# adapter.net
KiCad netlist of a schematic drawn in EAGLE
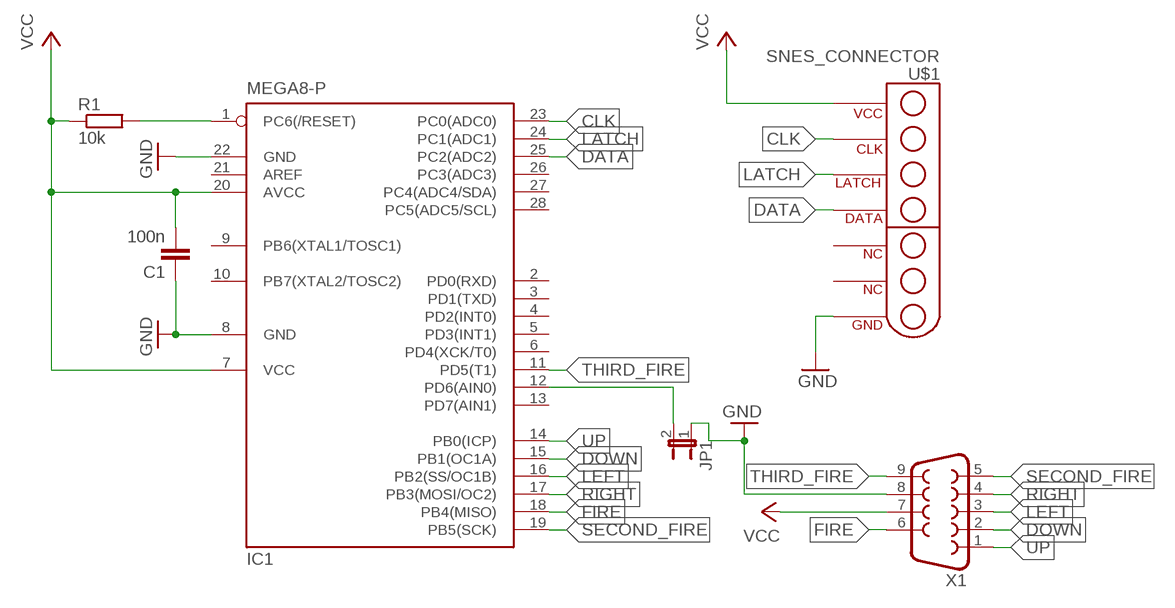
[diagram p0: schematic, sheet 1]

(export (version "E")
  (design (tool "Eeschema 10.0.6"))
  (components
    (comp (ref "C1")
      (value "100n")
      (footprint "eagle-import:C025-025X050")
      (libsource (lib "eagle-import") (part "C-EU025-025X050"))
    )
    (comp (ref "IC1")
      (value "MEGA8-P")
      (footprint "eagle-import:DIL28-3")
      (libsource (lib "eagle-import") (part "MEGA8-P"))
    )
    (comp (ref "JP1")
      (value "JP1E")
      (footprint "eagle-import:JP1")
      (libsource (lib "eagle-import") (part "JP1E"))
    )
    (comp (ref "R1")
      (value "10k")
      (footprint "eagle-import:0207_10")
      (libsource (lib "eagle-import") (part "R-EU_0207/10"))
    )
    (comp (ref "U$1")
      (value "SNES_CONNECTOR")
      (footprint "eagle-import:SNES_CONNECTOR")
      (libsource (lib "eagle-import") (part "SNES_CONNECTOR"))
    )
    (comp (ref "X1")
      (value "F09D")
      (footprint "eagle-import:F09D")
      (libsource (lib "eagle-import") (part "F09D"))
    )
  )
  (nets
    (net (code "1") (name "CLK") (class "Default")
      (node (ref "IC1") (pin "23") (pinfunction "PC0(ADC0)_23") (pintype "bidirectional"))
      (node (ref "U$1") (pin "P$9") (pinfunction "CLK_P$9") (pintype "input"))
    )
    (net (code "2") (name "DATA") (class "Default")
      (node (ref "IC1") (pin "25") (pinfunction "PC2(ADC2)_25") (pintype "bidirectional"))
      (node (ref "U$1") (pin "P$11") (pinfunction "DATA_P$11") (pintype "output"))
    )
    (net (code "3") (name "DOWN") (class "Default")
      (node (ref "IC1") (pin "15") (pinfunction "PB1(OC1A)_15") (pintype "bidirectional"))
      (node (ref "X1") (pin "2") (pinfunction "2_2") (pintype "passive"))
    )
    (net (code "4") (name "FIRE") (class "Default")
      (node (ref "IC1") (pin "18") (pinfunction "PB4(MISO)_18") (pintype "bidirectional"))
      (node (ref "X1") (pin "6") (pinfunction "6_6") (pintype "passive"))
    )
    (net (code "5") (name "GND") (class "Default")
      (node (ref "C1") (pin "1") (pinfunction "1_1") (pintype "passive"))
      (node (ref "IC1") (pin "22") (pinfunction "GND_22") (pintype "power_in"))
      (node (ref "IC1") (pin "8") (pinfunction "GND_8") (pintype "power_in"))
      (node (ref "JP1") (pin "1") (pinfunction "1_1") (pintype "passive"))
      (node (ref "U$1") (pin "P$14") (pinfunction "GND_P$14") (pintype "passive"))
      (node (ref "X1") (pin "8") (pinfunction "8_8") (pintype "passive"))
    )
    (net (code "6") (name "LATCH") (class "Default")
      (node (ref "IC1") (pin "24") (pinfunction "PC1(ADC1)_24") (pintype "bidirectional"))
      (node (ref "U$1") (pin "P$10") (pinfunction "LATCH_P$10") (pintype "input"))
    )
    (net (code "7") (name "LEFT") (class "Default")
      (node (ref "IC1") (pin "16") (pinfunction "PB2(SS/OC1B)_16") (pintype "bidirectional"))
      (node (ref "X1") (pin "3") (pinfunction "3_3") (pintype "passive"))
    )
    (net (code "8") (name "Net-(IC1-PC6({slash}RESET))") (class "Default")
      (node (ref "IC1") (pin "1") (pinfunction "PC6(/RESET)_1") (pintype "bidirectional"))
      (node (ref "R1") (pin "2") (pinfunction "2_2") (pintype "passive"))
    )
    (net (code "9") (name "Net-(IC1-PD6(AIN0))") (class "Default")
      (node (ref "IC1") (pin "12") (pinfunction "PD6(AIN0)_12") (pintype "bidirectional"))
      (node (ref "JP1") (pin "2") (pinfunction "2_2") (pintype "passive"))
    )
    (net (code "10") (name "RIGHT") (class "Default")
      (node (ref "IC1") (pin "17") (pinfunction "PB3(MOSI/OC2)_17") (pintype "bidirectional"))
      (node (ref "X1") (pin "4") (pinfunction "4_4") (pintype "passive"))
    )
    (net (code "11") (name "SECOND_FIRE") (class "Default")
      (node (ref "IC1") (pin "19") (pinfunction "PB5(SCK)_19") (pintype "bidirectional"))
      (node (ref "X1") (pin "5") (pinfunction "5_5") (pintype "passive"))
    )
    (net (code "12") (name "THIRD_FIRE") (class "Default")
      (node (ref "IC1") (pin "11") (pinfunction "PD5(T1)_11") (pintype "bidirectional"))
      (node (ref "X1") (pin "9") (pinfunction "9_9") (pintype "passive"))
    )
    (net (code "13") (name "UP") (class "Default")
      (node (ref "IC1") (pin "14") (pinfunction "PB0(ICP)_14") (pintype "bidirectional"))
      (node (ref "X1") (pin "1") (pinfunction "1_1") (pintype "passive"))
    )
    (net (code "14") (name "VCC") (class "Default")
      (node (ref "C1") (pin "2") (pinfunction "2_2") (pintype "passive"))
      (node (ref "IC1") (pin "20") (pinfunction "AVCC_20") (pintype "power_in"))
      (node (ref "IC1") (pin "7") (pinfunction "VCC_7") (pintype "power_in"))
      (node (ref "R1") (pin "1") (pinfunction "1_1") (pintype "passive"))
      (node (ref "U$1") (pin "P$8") (pinfunction "VCC_P$8") (pintype "power_in"))
      (node (ref "X1") (pin "7") (pinfunction "7_7") (pintype "passive"))
    )
    (net (code "15") (name "unconnected-(IC1-AREF-Pad21)") (class "Default")
      (node (ref "IC1") (pin "21") (pinfunction "AREF_21") (pintype "passive"))
    )
    (net (code "16") (name "unconnected-(IC1-PB6(XTAL1{slash}TOSC1)-Pad9)") (class "Default")
      (node (ref "IC1") (pin "9") (pinfunction "PB6(XTAL1/TOSC1)_9") (pintype "bidirectional"))
    )
    (net (code "17") (name "unconnected-(IC1-PB7(XTAL2{slash}TOSC2)-Pad10)") (class "Default")
      (node (ref "IC1") (pin "10") (pinfunction "PB7(XTAL2/TOSC2)_10") (pintype "bidirectional"))
    )
    (net (code "18") (name "unconnected-(IC1-PC3(ADC3)-Pad26)") (class "Default")
      (node (ref "IC1") (pin "26") (pinfunction "PC3(ADC3)_26") (pintype "bidirectional"))
    )
    (net (code "19") (name "unconnected-(IC1-PC4(ADC4{slash}SDA)-Pad27)") (class "Default")
      (node (ref "IC1") (pin "27") (pinfunction "PC4(ADC4/SDA)_27") (pintype "bidirectional"))
    )
    (net (code "20") (name "unconnected-(IC1-PC5(ADC5{slash}SCL)-Pad28)") (class "Default")
      (node (ref "IC1") (pin "28") (pinfunction "PC5(ADC5/SCL)_28") (pintype "bidirectional"))
    )
    (net (code "21") (name "unconnected-(IC1-PD0(RXD)-Pad2)") (class "Default")
      (node (ref "IC1") (pin "2") (pinfunction "PD0(RXD)_2") (pintype "bidirectional"))
    )
    (net (code "22") (name "unconnected-(IC1-PD1(TXD)-Pad3)") (class "Default")
      (node (ref "IC1") (pin "3") (pinfunction "PD1(TXD)_3") (pintype "bidirectional"))
    )
    (net (code "23") (name "unconnected-(IC1-PD2(INT0)-Pad4)") (class "Default")
      (node (ref "IC1") (pin "4") (pinfunction "PD2(INT0)_4") (pintype "bidirectional"))
    )
    (net (code "24") (name "unconnected-(IC1-PD3(INT1)-Pad5)") (class "Default")
      (node (ref "IC1") (pin "5") (pinfunction "PD3(INT1)_5") (pintype "bidirectional"))
    )
    (net (code "25") (name "unconnected-(IC1-PD4(XCK{slash}T0)-Pad6)") (class "Default")
      (node (ref "IC1") (pin "6") (pinfunction "PD4(XCK/T0)_6") (pintype "bidirectional"))
    )
    (net (code "26") (name "unconnected-(IC1-PD7(AIN1)-Pad13)") (class "Default")
      (node (ref "IC1") (pin "13") (pinfunction "PD7(AIN1)_13") (pintype "bidirectional"))
    )
    (net (code "27") (name "unconnected-(U$1-NC1-PadP$12)") (class "Default")
      (node (ref "U$1") (pin "P$12") (pinfunction "NC1_P$12") (pintype "no_connect"))
    )
    (net (code "28") (name "unconnected-(U$1-NC2-PadP$13)") (class "Default")
      (node (ref "U$1") (pin "P$13") (pinfunction "NC2_P$13") (pintype "no_connect"))
    )
  )
)
